# esp32_c6_a1_power.net
KiCad netlist of a schematic drawn in Altium Designer
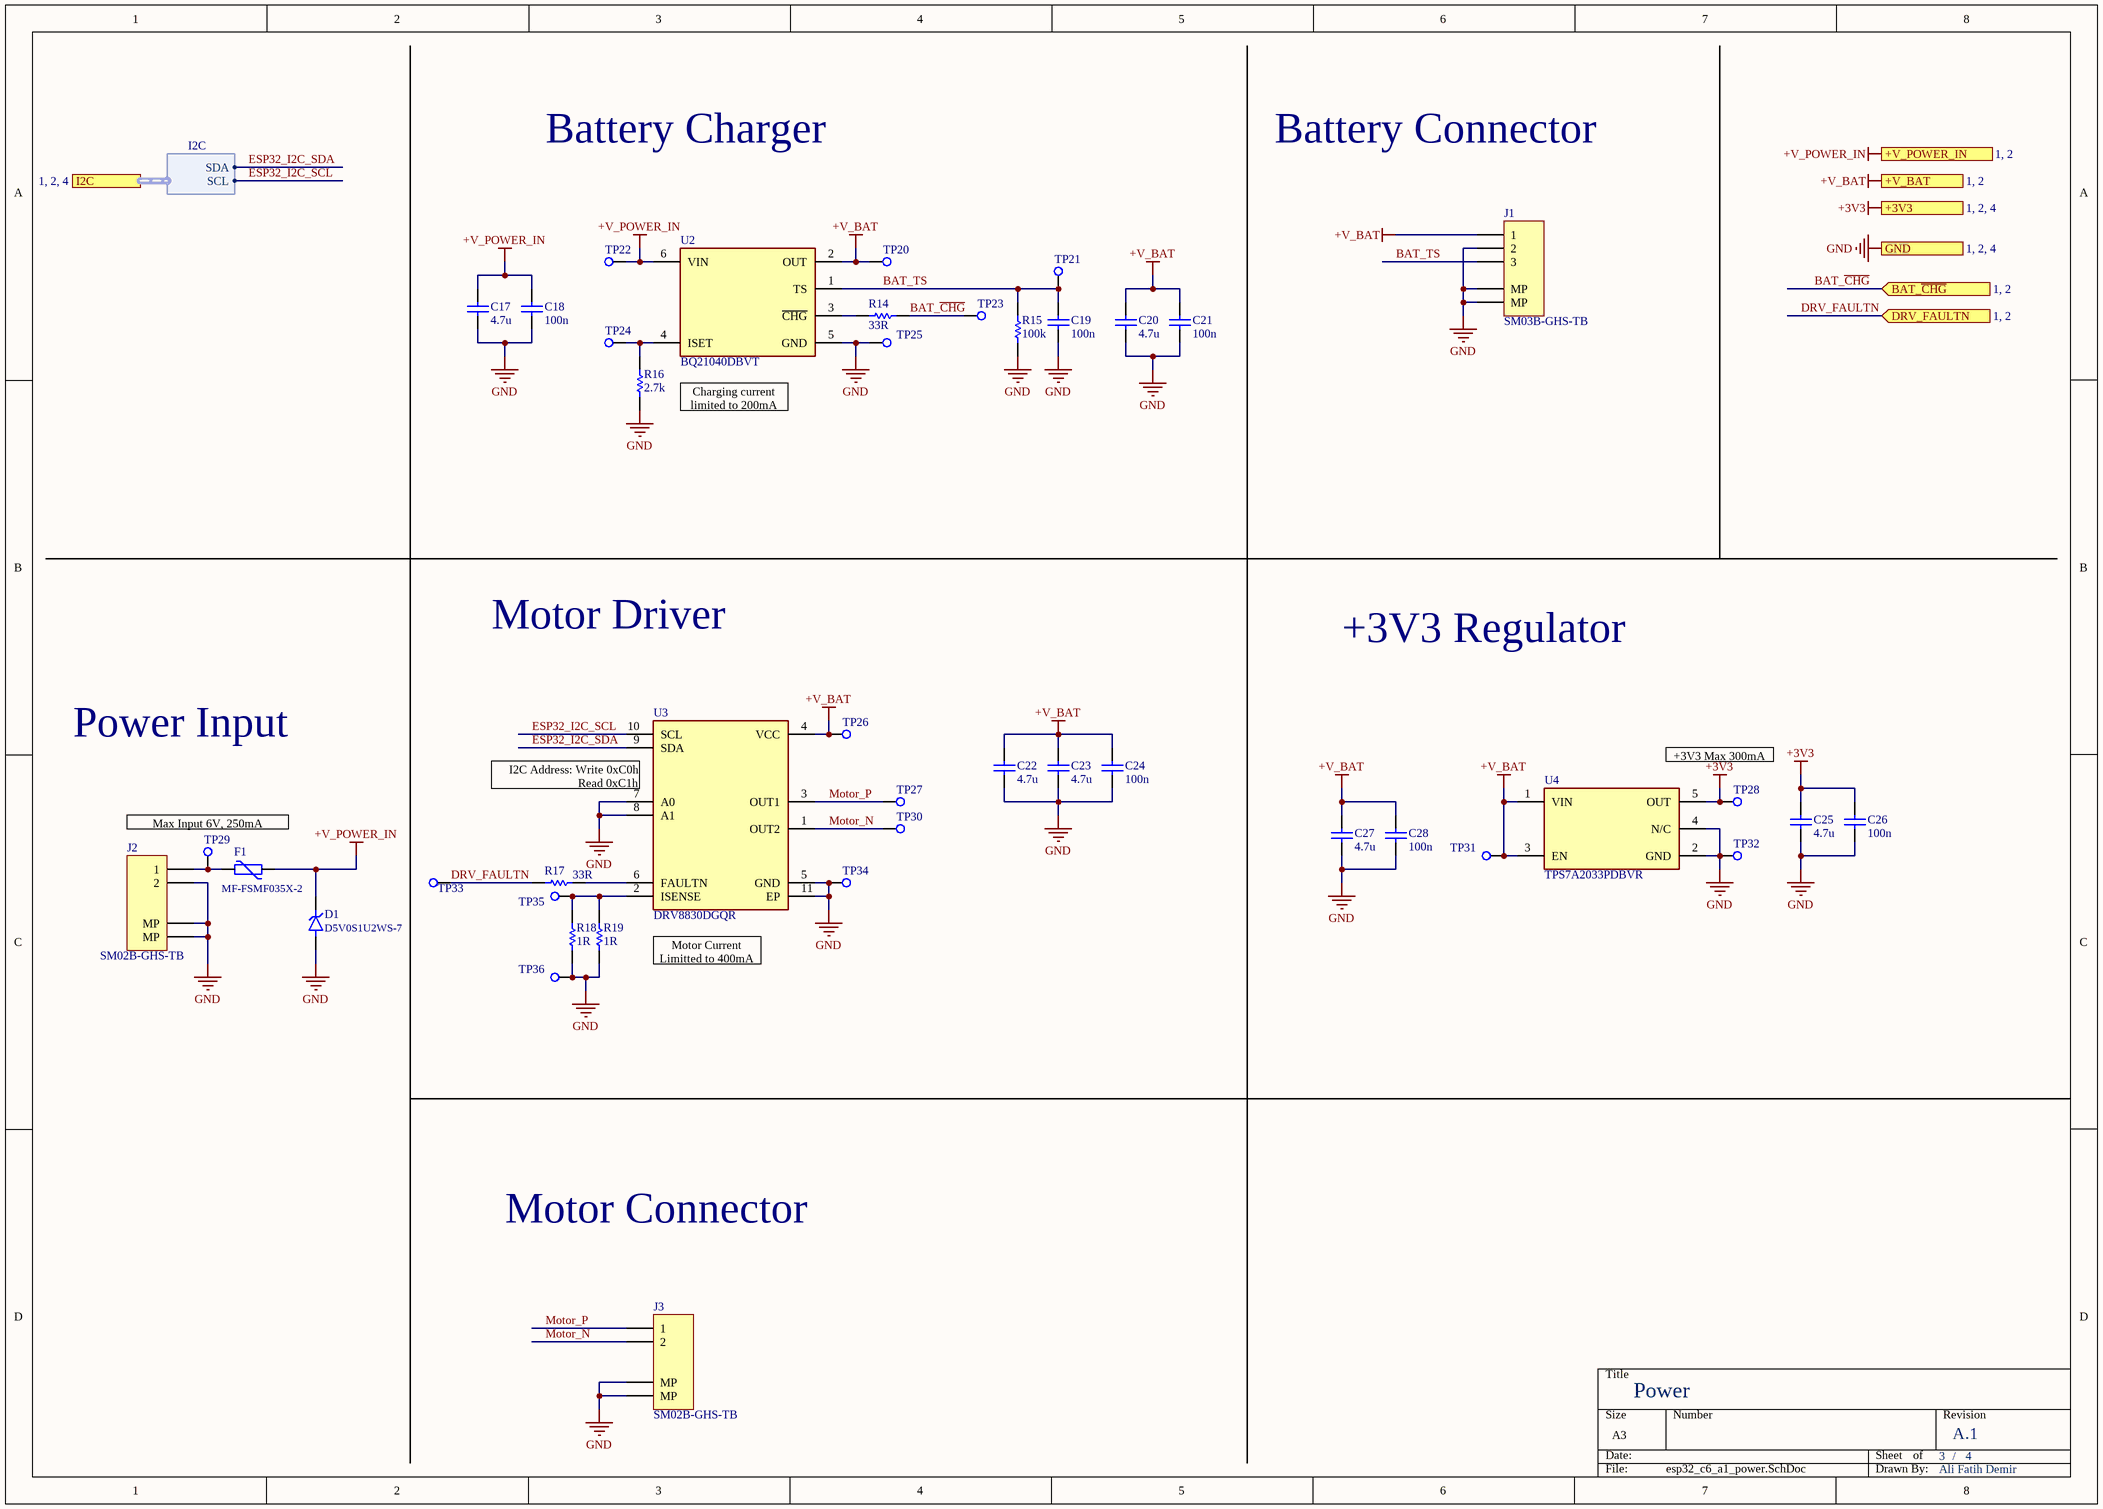
[diagram p0: esp32_c6_a1_power.SchDoc]

(export (version "E")
  (design (tool "Eeschema 10.0.6"))
  (components
    (comp (ref "C17")
      (value "4.7u")
      (footprint "C_0603")
      (description "SMD 0603 Ceramic Chip Capacitor")
      (fields (field (name "MANUFACTURER") "Samsung") (field (name "PART NUMBER") "?"))
      (libsource (lib "afd_lib") (part "C_0603"))
    )
    (comp (ref "C18")
      (value "100n")
      (footprint "C_0402")
      (description "SMD 0402 Ceramic Chip Capacitor")
      (fields (field (name "MANUFACTURER") "Samsung") (field (name "PART NUMBER") "?"))
      (libsource (lib "afd_lib") (part "C_0402"))
    )
    (comp (ref "C19")
      (value "100n")
      (footprint "C_0402")
      (description "SMD 0402 Ceramic Chip Capacitor")
      (fields (field (name "MANUFACTURER") "Samsung") (field (name "PART NUMBER") "?"))
      (libsource (lib "afd_lib") (part "C_0402"))
    )
    (comp (ref "C20")
      (value "4.7u")
      (footprint "C_0603")
      (description "SMD 0603 Ceramic Chip Capacitor")
      (fields (field (name "MANUFACTURER") "Samsung") (field (name "PART NUMBER") "?"))
      (libsource (lib "afd_lib") (part "C_0603"))
    )
    (comp (ref "C21")
      (value "100n")
      (footprint "C_0402")
      (description "SMD 0402 Ceramic Chip Capacitor")
      (fields (field (name "MANUFACTURER") "Samsung") (field (name "PART NUMBER") "?"))
      (libsource (lib "afd_lib") (part "C_0402"))
    )
    (comp (ref "C22")
      (value "4.7u")
      (footprint "C_0603")
      (description "SMD 0603 Ceramic Chip Capacitor")
      (fields (field (name "MANUFACTURER") "Samsung") (field (name "PART NUMBER") "?"))
      (libsource (lib "afd_lib") (part "C_0603"))
    )
    (comp (ref "C23")
      (value "4.7u")
      (footprint "C_0603")
      (description "SMD 0603 Ceramic Chip Capacitor")
      (fields (field (name "MANUFACTURER") "Samsung") (field (name "PART NUMBER") "?"))
      (libsource (lib "afd_lib") (part "C_0603"))
    )
    (comp (ref "C24")
      (value "100n")
      (footprint "C_0402")
      (description "SMD 0402 Ceramic Chip Capacitor")
      (fields (field (name "MANUFACTURER") "Samsung") (field (name "PART NUMBER") "?"))
      (libsource (lib "afd_lib") (part "C_0402"))
    )
    (comp (ref "C25")
      (value "4.7u")
      (footprint "C_0603")
      (description "SMD 0603 Ceramic Chip Capacitor")
      (fields (field (name "MANUFACTURER") "Samsung") (field (name "PART NUMBER") "?"))
      (libsource (lib "afd_lib") (part "C_0603"))
    )
    (comp (ref "C26")
      (value "100n")
      (footprint "C_0402")
      (description "SMD 0402 Ceramic Chip Capacitor")
      (fields (field (name "MANUFACTURER") "Samsung") (field (name "PART NUMBER") "?"))
      (libsource (lib "afd_lib") (part "C_0402"))
    )
    (comp (ref "C27")
      (value "4.7u")
      (footprint "C_0603")
      (description "SMD 0603 Ceramic Chip Capacitor")
      (fields (field (name "MANUFACTURER") "Samsung") (field (name "PART NUMBER") "?"))
      (libsource (lib "afd_lib") (part "C_0603"))
    )
    (comp (ref "C28")
      (value "100n")
      (footprint "C_0402")
      (description "SMD 0402 Ceramic Chip Capacitor")
      (fields (field (name "MANUFACTURER") "Samsung") (field (name "PART NUMBER") "?"))
      (libsource (lib "afd_lib") (part "C_0402"))
    )
    (comp (ref "D1")
      (value "D5V0S1U2WS-7")
      (footprint "SOD2513X120N")
      (description "16V Clamp 70A (8/20µs) Ipp Tvs Diode Surface Mount SOD-323")
      (fields (field (name "MANUFACTURER") "Diodes") (field (name "MPN") "BZV55C4V7-TP"))
      (libsource (lib "afd_lib") (part "D5V0S1U2WS-7"))
    )
    (comp (ref "F1")
      (value "MF-FSMF035X-2")
      (footprint "0603-F1608X100N")
      (description "Polymeric PTC Resettable Fuse 6V 350mA Ih Surface Mount 0603 _1608 Metric_, Concave")
      (fields (field (name "MANUFACTURER") "Bourns"))
      (libsource (lib "afd_lib") (part "MF-FSMF035X-2"))
    )
    (comp (ref "J1")
      (value "SM03B-GHS-TB")
      (footprint "jst_sm03b-ghs-tb")
      (description "CONN HEADER SMD 3POS 1.25MM")
      (fields (field (name "MANUFACTURER") "JST"))
      (libsource (lib "afd_lib") (part "SM03B-GHS-TB"))
    )
    (comp (ref "J2")
      (value "SM02B-GHS-TB")
      (footprint "JST-SM02B-GHS-TB")
      (description "CONN HEADER SMD 2POS 1.25MM")
      (fields (field (name "MANUFACTURER") "JST"))
      (libsource (lib "") (part "SM02B-GHS-TB_1"))
    )
    (comp (ref "J3")
      (value "SM02B-GHS-TB")
      (footprint "JST-SM02B-GHS-TB")
      (description "CONN HEADER SMD 2POS 1.25MM")
      (fields (field (name "MANUFACTURER") "JST"))
      (libsource (lib "afd_lib") (part "SM02B-GHS-TB"))
    )
    (comp (ref "R14")
      (value "33R")
      (footprint "R_0402")
      (description "SMD 0402 Rectangular Thick Film Chip Resistor")
      (fields (field (name "MANUFACTURER") "Yageo") (field (name "PART NUMBER") "?"))
      (libsource (lib "afd_lib") (part "R_0402"))
    )
    (comp (ref "R15")
      (value "100k")
      (footprint "R_0402")
      (description "SMD 0402 Rectangular Thick Film Chip Resistor")
      (fields (field (name "MANUFACTURER") "Yageo") (field (name "PART NUMBER") "?"))
      (libsource (lib "afd_lib") (part "R_0402"))
    )
    (comp (ref "R16")
      (value "2.7k")
      (footprint "R_0402")
      (description "SMD 0402 Rectangular Thick Film Chip Resistor")
      (fields (field (name "MANUFACTURER") "Yageo") (field (name "PART NUMBER") "?"))
      (libsource (lib "afd_lib") (part "R_0402"))
    )
    (comp (ref "R17")
      (value "33R")
      (footprint "R_0402")
      (description "SMD 0402 Rectangular Thick Film Chip Resistor")
      (fields (field (name "MANUFACTURER") "Yageo") (field (name "PART NUMBER") "?"))
      (libsource (lib "afd_lib") (part "R_0402"))
    )
    (comp (ref "R18")
      (value "1R")
      (footprint "R_0603")
      (description "SMD 0603 Rectangular Thick Film Chip Resistor")
      (fields (field (name "MANUFACTURER") "Yageo") (field (name "PART NUMBER") "?"))
      (libsource (lib "afd_lib") (part "R_0603"))
    )
    (comp (ref "R19")
      (value "1R")
      (footprint "R_0603")
      (description "SMD 0603 Rectangular Thick Film Chip Resistor")
      (fields (field (name "MANUFACTURER") "Yageo") (field (name "PART NUMBER") "?"))
      (libsource (lib "afd_lib") (part "R_0603"))
    )
    (comp (ref "TP20")
      (value "TP")
      (footprint "tp_round_80")
      (description "Test Point")
      (libsource (lib "afd_lib") (part "TP"))
    )
    (comp (ref "TP21")
      (value "TP")
      (footprint "tp_round_80")
      (description "Test Point")
      (libsource (lib "afd_lib") (part "TP"))
    )
    (comp (ref "TP22")
      (value "TP")
      (footprint "tp_round_80")
      (description "Test Point")
      (libsource (lib "afd_lib") (part "TP"))
    )
    (comp (ref "TP23")
      (value "TP")
      (footprint "tp_round_80")
      (description "Test Point")
      (libsource (lib "afd_lib") (part "TP"))
    )
    (comp (ref "TP24")
      (value "TP")
      (footprint "tp_round_80")
      (description "Test Point")
      (libsource (lib "afd_lib") (part "TP"))
    )
    (comp (ref "TP25")
      (value "TP")
      (footprint "tp_round_80")
      (description "Test Point")
      (libsource (lib "afd_lib") (part "TP"))
    )
    (comp (ref "TP26")
      (value "TP")
      (footprint "tp_round_80")
      (description "Test Point")
      (libsource (lib "afd_lib") (part "TP"))
    )
    (comp (ref "TP27")
      (value "TP")
      (footprint "tp_round_80")
      (description "Test Point")
      (libsource (lib "afd_lib") (part "TP"))
    )
    (comp (ref "TP28")
      (value "TP")
      (footprint "tp_round_80")
      (description "Test Point")
      (libsource (lib "afd_lib") (part "TP"))
    )
    (comp (ref "TP29")
      (value "TP")
      (footprint "tp_round_80")
      (description "Test Point")
      (libsource (lib "afd_lib") (part "TP"))
    )
    (comp (ref "TP30")
      (value "TP")
      (footprint "tp_round_80")
      (description "Test Point")
      (libsource (lib "afd_lib") (part "TP"))
    )
    (comp (ref "TP31")
      (value "TP")
      (footprint "tp_round_80")
      (description "Test Point")
      (libsource (lib "afd_lib") (part "TP"))
    )
    (comp (ref "TP32")
      (value "TP")
      (footprint "tp_round_80")
      (description "Test Point")
      (libsource (lib "afd_lib") (part "TP"))
    )
    (comp (ref "TP33")
      (value "TP")
      (footprint "tp_round_80")
      (description "Test Point")
      (libsource (lib "afd_lib") (part "TP"))
    )
    (comp (ref "TP34")
      (value "TP")
      (footprint "tp_round_80")
      (description "Test Point")
      (libsource (lib "afd_lib") (part "TP"))
    )
    (comp (ref "TP35")
      (value "TP")
      (footprint "tp_round_80")
      (description "Test Point")
      (libsource (lib "afd_lib") (part "TP"))
    )
    (comp (ref "TP36")
      (value "TP")
      (footprint "tp_round_80")
      (description "Test Point")
      (libsource (lib "afd_lib") (part "TP"))
    )
    (comp (ref "U2")
      (value "BQ21040DBVT")
      (footprint "SOT95P280X110-6N")
      (description "1-cell, 0.8-A Li-ion and Li-polymerymer battery charger 6-SOT-23 0 to 125")
      (fields (field (name "DIGI-KEY_PART_NUMBER") "296-44196-1-ND") (field (name "MF") "Texas Instruments"))
      (libsource (lib "afd_lib") (part "BQ21040DBVT"))
    )
    (comp (ref "U3")
      (value "DRV8830DGQR")
      (footprint "IC_XTR111AIDGQR")
      (description "6.8-V, 1-A H-bridge motor driver with speed regulation and i2c control 10-HVSSOP -40 to 85")
      (fields (field (name "MANUFACTURER") "Texas Instruments"))
      (libsource (lib "afd_lib") (part "DRV8830DGQR"))
    )
    (comp (ref "U4")
      (value "TPS7A2033PDBVR")
      (footprint "SOT95P280X110-5N")
      (description "Linear Voltage Regulator IC Positive Fixed 1 Output 300mA SOT-23-5")
      (fields (field (name "MANUFACTURER") "Texas Instruments"))
      (libsource (lib "afd_lib") (part "TPS7A2033PDBVR"))
    )
  )
  (nets
    (net (code "2") (name "+3V3") (class "Default")
      (node (ref "C25") (pin "2") (pinfunction "2_2") (pintype "passive"))
      (node (ref "C26") (pin "2") (pinfunction "2_2") (pintype "passive"))
      (node (ref "TP28") (pin "1") (pinfunction "1_1") (pintype "passive"))
      (node (ref "U4") (pin "5") (pinfunction "OUT_5") (pintype "passive"))
    )
    (net (code "3") (name "+V_BAT") (class "Default")
      (node (ref "C20") (pin "2") (pinfunction "2_2") (pintype "passive"))
      (node (ref "C21") (pin "2") (pinfunction "2_2") (pintype "passive"))
      (node (ref "C22") (pin "2") (pinfunction "2_2") (pintype "passive"))
      (node (ref "C23") (pin "2") (pinfunction "2_2") (pintype "passive"))
      (node (ref "C24") (pin "2") (pinfunction "2_2") (pintype "passive"))
      (node (ref "C27") (pin "2") (pinfunction "2_2") (pintype "passive"))
      (node (ref "C28") (pin "2") (pinfunction "2_2") (pintype "passive"))
      (node (ref "J1") (pin "1") (pinfunction "1_1") (pintype "passive"))
      (node (ref "TP20") (pin "1") (pinfunction "1_1") (pintype "passive"))
      (node (ref "TP26") (pin "1") (pinfunction "1_1") (pintype "passive"))
      (node (ref "TP31") (pin "1") (pinfunction "1_1") (pintype "passive"))
      (node (ref "U2") (pin "2") (pinfunction "OUT_2") (pintype "passive"))
      (node (ref "U3") (pin "4") (pinfunction "VCC_4") (pintype "passive"))
      (node (ref "U4") (pin "1") (pinfunction "VIN_1") (pintype "passive"))
      (node (ref "U4") (pin "3") (pinfunction "EN_3") (pintype "passive"))
    )
    (net (code "4") (name "+V_POWER_IN") (class "Default")
      (node (ref "C17") (pin "2") (pinfunction "2_2") (pintype "passive"))
      (node (ref "C18") (pin "2") (pinfunction "2_2") (pintype "passive"))
      (node (ref "D1") (pin "1") (pinfunction "1_1") (pintype "passive"))
      (node (ref "F1") (pin "1") (pinfunction "1_1") (pintype "passive"))
      (node (ref "TP22") (pin "1") (pinfunction "1_1") (pintype "passive"))
      (node (ref "U2") (pin "6") (pinfunction "VIN_6") (pintype "passive"))
    )
    (net (code "5") (name "/BAT_TS") (class "Default")
      (node (ref "C19") (pin "2") (pinfunction "2_2") (pintype "passive"))
      (node (ref "J1") (pin "3") (pinfunction "3_3") (pintype "passive"))
      (node (ref "R15") (pin "1") (pinfunction "1_1") (pintype "passive"))
      (node (ref "TP21") (pin "1") (pinfunction "1_1") (pintype "passive"))
      (node (ref "U2") (pin "1") (pinfunction "TS_1") (pintype "passive"))
    )
    (net (code "6") (name "/BAT_~{CHG}") (class "Default")
      (node (ref "R14") (pin "1") (pinfunction "1_1") (pintype "passive"))
      (node (ref "TP23") (pin "1") (pinfunction "1_1") (pintype "passive"))
    )
    (net (code "7") (name "/DRV_FAULTN") (class "Default")
      (node (ref "R17") (pin "2") (pinfunction "2_2") (pintype "passive"))
      (node (ref "TP33") (pin "1") (pinfunction "1_1") (pintype "passive"))
    )
    (net (code "8") (name "/ESP32_I2C_SCL") (class "Default")
      (node (ref "U3") (pin "10") (pinfunction "SCL_10") (pintype "passive"))
    )
    (net (code "9") (name "/ESP32_I2C_SDA") (class "Default")
      (node (ref "U3") (pin "9") (pinfunction "SDA_9") (pintype "passive"))
    )
    (net (code "10") (name "/Motor_N") (class "Default")
      (node (ref "J3") (pin "2") (pinfunction "2_2") (pintype "passive"))
      (node (ref "TP30") (pin "1") (pinfunction "1_1") (pintype "passive"))
      (node (ref "U3") (pin "1") (pinfunction "OUT2_1") (pintype "passive"))
    )
    (net (code "11") (name "/Motor_P") (class "Default")
      (node (ref "J3") (pin "1") (pinfunction "1_1") (pintype "passive"))
      (node (ref "TP27") (pin "1") (pinfunction "1_1") (pintype "passive"))
      (node (ref "U3") (pin "3") (pinfunction "OUT1_3") (pintype "passive"))
    )
    (net (code "13") (name "GND") (class "Default")
      (node (ref "C17") (pin "1") (pinfunction "1_1") (pintype "passive"))
      (node (ref "C18") (pin "1") (pinfunction "1_1") (pintype "passive"))
      (node (ref "C19") (pin "1") (pinfunction "1_1") (pintype "passive"))
      (node (ref "C20") (pin "1") (pinfunction "1_1") (pintype "passive"))
      (node (ref "C21") (pin "1") (pinfunction "1_1") (pintype "passive"))
      (node (ref "C22") (pin "1") (pinfunction "1_1") (pintype "passive"))
      (node (ref "C23") (pin "1") (pinfunction "1_1") (pintype "passive"))
      (node (ref "C24") (pin "1") (pinfunction "1_1") (pintype "passive"))
      (node (ref "C25") (pin "1") (pinfunction "1_1") (pintype "passive"))
      (node (ref "C26") (pin "1") (pinfunction "1_1") (pintype "passive"))
      (node (ref "C27") (pin "1") (pinfunction "1_1") (pintype "passive"))
      (node (ref "C28") (pin "1") (pinfunction "1_1") (pintype "passive"))
      (node (ref "D1") (pin "2") (pinfunction "2_2") (pintype "passive"))
      (node (ref "J1") (pin "2") (pinfunction "2_2") (pintype "passive"))
      (node (ref "J1") (pin "MP1") (pinfunction "MP_MP1") (pintype "passive"))
      (node (ref "J1") (pin "MP2") (pinfunction "MP_MP2") (pintype "passive"))
      (node (ref "J2") (pin "2") (pinfunction "2_2") (pintype "passive"))
      (node (ref "J2") (pin "MP1") (pinfunction "MP_MP1") (pintype "passive"))
      (node (ref "J2") (pin "MP2") (pinfunction "MP_MP2") (pintype "passive"))
      (node (ref "J3") (pin "MP1") (pinfunction "MP_MP1") (pintype "passive"))
      (node (ref "J3") (pin "MP2") (pinfunction "MP_MP2") (pintype "passive"))
      (node (ref "R15") (pin "2") (pinfunction "2_2") (pintype "passive"))
      (node (ref "R16") (pin "2") (pinfunction "2_2") (pintype "passive"))
      (node (ref "R18") (pin "1") (pinfunction "1_1") (pintype "passive"))
      (node (ref "R19") (pin "1") (pinfunction "1_1") (pintype "passive"))
      (node (ref "TP25") (pin "1") (pinfunction "1_1") (pintype "passive"))
      (node (ref "TP32") (pin "1") (pinfunction "1_1") (pintype "passive"))
      (node (ref "TP34") (pin "1") (pinfunction "1_1") (pintype "passive"))
      (node (ref "TP36") (pin "1") (pinfunction "1_1") (pintype "passive"))
      (node (ref "U2") (pin "5") (pinfunction "GND_5") (pintype "passive"))
      (node (ref "U3") (pin "11") (pinfunction "EP_11") (pintype "passive"))
      (node (ref "U3") (pin "5") (pinfunction "GND_5") (pintype "passive"))
      (node (ref "U3") (pin "7") (pinfunction "A0_7") (pintype "passive"))
      (node (ref "U3") (pin "8") (pinfunction "A1_8") (pintype "passive"))
      (node (ref "U4") (pin "2") (pinfunction "GND_2") (pintype "power_in"))
      (node (ref "U4") (pin "4") (pinfunction "N/C_4") (pintype "power_in"))
    )
    (net (code "14") (name "Net-(F1-Pad2)") (class "Default")
      (node (ref "F1") (pin "2") (pinfunction "2_2") (pintype "passive"))
      (node (ref "J2") (pin "1") (pinfunction "1_1") (pintype "passive"))
      (node (ref "TP29") (pin "1") (pinfunction "1_1") (pintype "passive"))
    )
    (net (code "15") (name "Net-(U2-ISET)") (class "Default")
      (node (ref "R16") (pin "1") (pinfunction "1_1") (pintype "passive"))
      (node (ref "TP24") (pin "1") (pinfunction "1_1") (pintype "passive"))
      (node (ref "U2") (pin "4") (pinfunction "ISET_4") (pintype "passive"))
    )
    (net (code "16") (name "Net-(U2-~{CHG})") (class "Default")
      (node (ref "R14") (pin "2") (pinfunction "2_2") (pintype "passive"))
      (node (ref "U2") (pin "3") (pinfunction "~{CHG}_3") (pintype "passive"))
    )
    (net (code "17") (name "Net-(U3-FAULTN)") (class "Default")
      (node (ref "R17") (pin "1") (pinfunction "1_1") (pintype "passive"))
      (node (ref "U3") (pin "6") (pinfunction "FAULTN_6") (pintype "passive"))
    )
    (net (code "18") (name "Net-(U3-ISENSE)") (class "Default")
      (node (ref "R18") (pin "2") (pinfunction "2_2") (pintype "passive"))
      (node (ref "R19") (pin "2") (pinfunction "2_2") (pintype "passive"))
      (node (ref "TP35") (pin "1") (pinfunction "1_1") (pintype "passive"))
      (node (ref "U3") (pin "2") (pinfunction "ISENSE_2") (pintype "passive"))
    )
  )
)
